# helloEcho.net
KiCad netlist of a schematic drawn in EAGLE
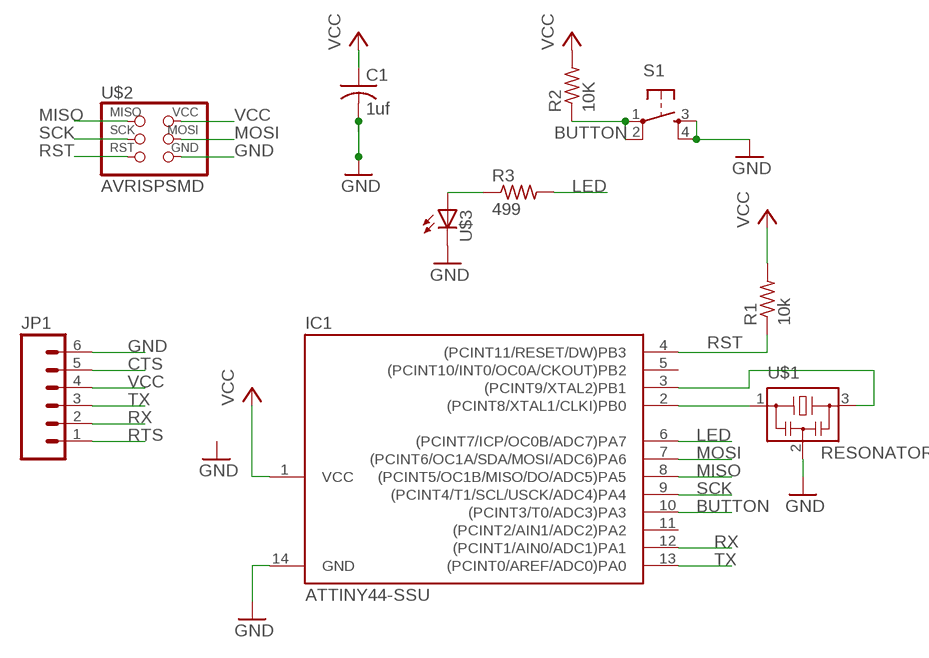
[diagram p0: schematic, sheet 1]

(export (version "E")
  (design (tool "Eeschema 10.0.6"))
  (components
    (comp (ref "C1")
      (value "1uf")
      (footprint "eagle-import:C1206")
      (libsource (lib "eagle-import") (part "C-USC1206"))
    )
    (comp (ref "IC1")
      (value "ATTINY44-SSU")
      (footprint "eagle-import:SOIC14")
      (libsource (lib "eagle-import") (part "ATTINY44-SSU"))
    )
    (comp (ref "JP1")
      (value "M06SMD")
      (footprint "eagle-import:1X06-SMD")
      (libsource (lib "eagle-import") (part "M06SMD"))
    )
    (comp (ref "R1")
      (value "10k")
      (footprint "eagle-import:R1206")
      (libsource (lib "eagle-import") (part "R-US_R1206"))
    )
    (comp (ref "R2")
      (value "10K")
      (footprint "eagle-import:1206")
      (libsource (lib "eagle-import") (part "RESISTOR1206"))
    )
    (comp (ref "R3")
      (value "499")
      (footprint "eagle-import:1206")
      (libsource (lib "eagle-import") (part "RESISTOR1206"))
    )
    (comp (ref "S1")
      (value "6MM_SWITCH6MM_SWITCH")
      (footprint "eagle-import:6MM_SWITCH")
      (libsource (lib "eagle-import") (part "6MM_SWITCH6MM_SWITCH"))
    )
    (comp (ref "U$1")
      (value "RESONATOR")
      (footprint "eagle-import:EFOBM")
      (libsource (lib "eagle-import") (part "RESONATOR"))
    )
    (comp (ref "U$2")
      (value "AVRISPSMD")
      (footprint "eagle-import:2X03SMD")
      (libsource (lib "eagle-import") (part "AVRISPSMD"))
    )
    (comp (ref "U$3")
      (value "LED1206")
      (footprint "eagle-import:1206")
      (libsource (lib "eagle-import") (part "LED1206"))
    )
  )
  (nets
    (net (code "1") (name "/BUTTON") (class "Default")
      (node (ref "IC1") (pin "10") (pinfunction "(PCINT3/T0/ADC3)PA3_10") (pintype "bidirectional"))
      (node (ref "R2") (pin "1") (pinfunction "1_1") (pintype "passive"))
      (node (ref "S1") (pin "1") (pinfunction "P_1") (pintype "passive"))
      (node (ref "S1") (pin "2") (pinfunction "P1_2") (pintype "passive"))
    )
    (net (code "2") (name "/CTS") (class "Default")
      (node (ref "JP1") (pin "5") (pinfunction "5_5") (pintype "passive"))
    )
    (net (code "3") (name "/LED") (class "Default")
      (node (ref "IC1") (pin "6") (pinfunction "(PCINT7/ICP/OC0B/ADC7)PA7_6") (pintype "bidirectional"))
      (node (ref "R3") (pin "2") (pinfunction "2_2") (pintype "passive"))
    )
    (net (code "4") (name "/MISO") (class "Default")
      (node (ref "IC1") (pin "8") (pinfunction "(PCINT5/OC1B/MISO/DO/ADC5)PA5_8") (pintype "bidirectional"))
      (node (ref "U$2") (pin "1") (pinfunction "MISO_1") (pintype "passive"))
    )
    (net (code "5") (name "/MOSI") (class "Default")
      (node (ref "IC1") (pin "7") (pinfunction "(PCINT6/OC1A/SDA/MOSI/ADC6)PA6_7") (pintype "bidirectional"))
      (node (ref "U$2") (pin "4") (pinfunction "MOSI_4") (pintype "passive"))
    )
    (net (code "6") (name "/RST") (class "Default")
      (node (ref "IC1") (pin "4") (pinfunction "(PCINT11/RESET/DW)PB3_4") (pintype "bidirectional"))
      (node (ref "R1") (pin "1") (pinfunction "1_1") (pintype "passive"))
      (node (ref "U$2") (pin "5") (pinfunction "RST_5") (pintype "passive"))
    )
    (net (code "7") (name "/RTS") (class "Default")
      (node (ref "JP1") (pin "1") (pinfunction "1_1") (pintype "passive"))
    )
    (net (code "8") (name "/RX") (class "Default")
      (node (ref "IC1") (pin "12") (pinfunction "(PCINT1/AIN0/ADC1)PA1_12") (pintype "bidirectional"))
      (node (ref "JP1") (pin "2") (pinfunction "2_2") (pintype "passive"))
    )
    (net (code "9") (name "/SCK") (class "Default")
      (node (ref "IC1") (pin "9") (pinfunction "(PCINT4/T1/SCL/USCK/ADC4)PA4_9") (pintype "bidirectional"))
      (node (ref "U$2") (pin "3") (pinfunction "SCK_3") (pintype "passive"))
    )
    (net (code "10") (name "/TX") (class "Default")
      (node (ref "IC1") (pin "13") (pinfunction "(PCINT0/AREF/ADC0)PA0_13") (pintype "bidirectional"))
      (node (ref "JP1") (pin "3") (pinfunction "3_3") (pintype "passive"))
    )
    (net (code "11") (name "GND") (class "Default")
      (node (ref "C1") (pin "2") (pinfunction "2_2") (pintype "passive"))
      (node (ref "IC1") (pin "14") (pinfunction "GND_14") (pintype "power_in"))
      (node (ref "JP1") (pin "6") (pinfunction "6_6") (pintype "passive"))
      (node (ref "S1") (pin "3") (pinfunction "S_3") (pintype "passive"))
      (node (ref "S1") (pin "4") (pinfunction "S1_4") (pintype "passive"))
      (node (ref "U$1") (pin "2") (pinfunction "2_2") (pintype "passive"))
      (node (ref "U$2") (pin "6") (pinfunction "GND_6") (pintype "passive"))
      (node (ref "U$3") (pin "2") (pinfunction "C_2") (pintype "passive"))
    )
    (net (code "12") (name "Net-(IC1-(PCINT8{slash}XTAL1{slash}CLKI)PB0)") (class "Default")
      (node (ref "IC1") (pin "2") (pinfunction "(PCINT8/XTAL1/CLKI)PB0_2") (pintype "bidirectional"))
      (node (ref "U$1") (pin "1") (pinfunction "1_1") (pintype "passive"))
    )
    (net (code "13") (name "Net-(IC1-(PCINT9{slash}XTAL2)PB1)") (class "Default")
      (node (ref "IC1") (pin "3") (pinfunction "(PCINT9/XTAL2)PB1_3") (pintype "bidirectional"))
      (node (ref "U$1") (pin "3") (pinfunction "3_3") (pintype "passive"))
    )
    (net (code "14") (name "Net-(U$3-A)") (class "Default")
      (node (ref "R3") (pin "1") (pinfunction "1_1") (pintype "passive"))
      (node (ref "U$3") (pin "1") (pinfunction "A_1") (pintype "passive"))
    )
    (net (code "15") (name "VCC") (class "Default")
      (node (ref "C1") (pin "1") (pinfunction "1_1") (pintype "passive"))
      (node (ref "IC1") (pin "1") (pinfunction "VCC_1") (pintype "power_in"))
      (node (ref "JP1") (pin "4") (pinfunction "4_4") (pintype "passive"))
      (node (ref "R1") (pin "2") (pinfunction "2_2") (pintype "passive"))
      (node (ref "R2") (pin "2") (pinfunction "2_2") (pintype "passive"))
      (node (ref "U$2") (pin "2") (pinfunction "VCC_2") (pintype "passive"))
    )
    (net (code "16") (name "unconnected-(IC1-(PCINT2{slash}AIN1{slash}ADC2)PA2-Pad11)") (class "Default")
      (node (ref "IC1") (pin "11") (pinfunction "(PCINT2/AIN1/ADC2)PA2_11") (pintype "bidirectional"))
    )
    (net (code "17") (name "unconnected-(IC1-(PCINT10{slash}INT0{slash}OC0A{slash}CKOUT)PB2-Pad5)") (class "Default")
      (node (ref "IC1") (pin "5") (pinfunction "(PCINT10/INT0/OC0A/CKOUT)PB2_5") (pintype "bidirectional"))
    )
  )
)
